# Konwerter_USB_RS232_4porty.net
KiCad netlist of a schematic drawn in Altium Designer
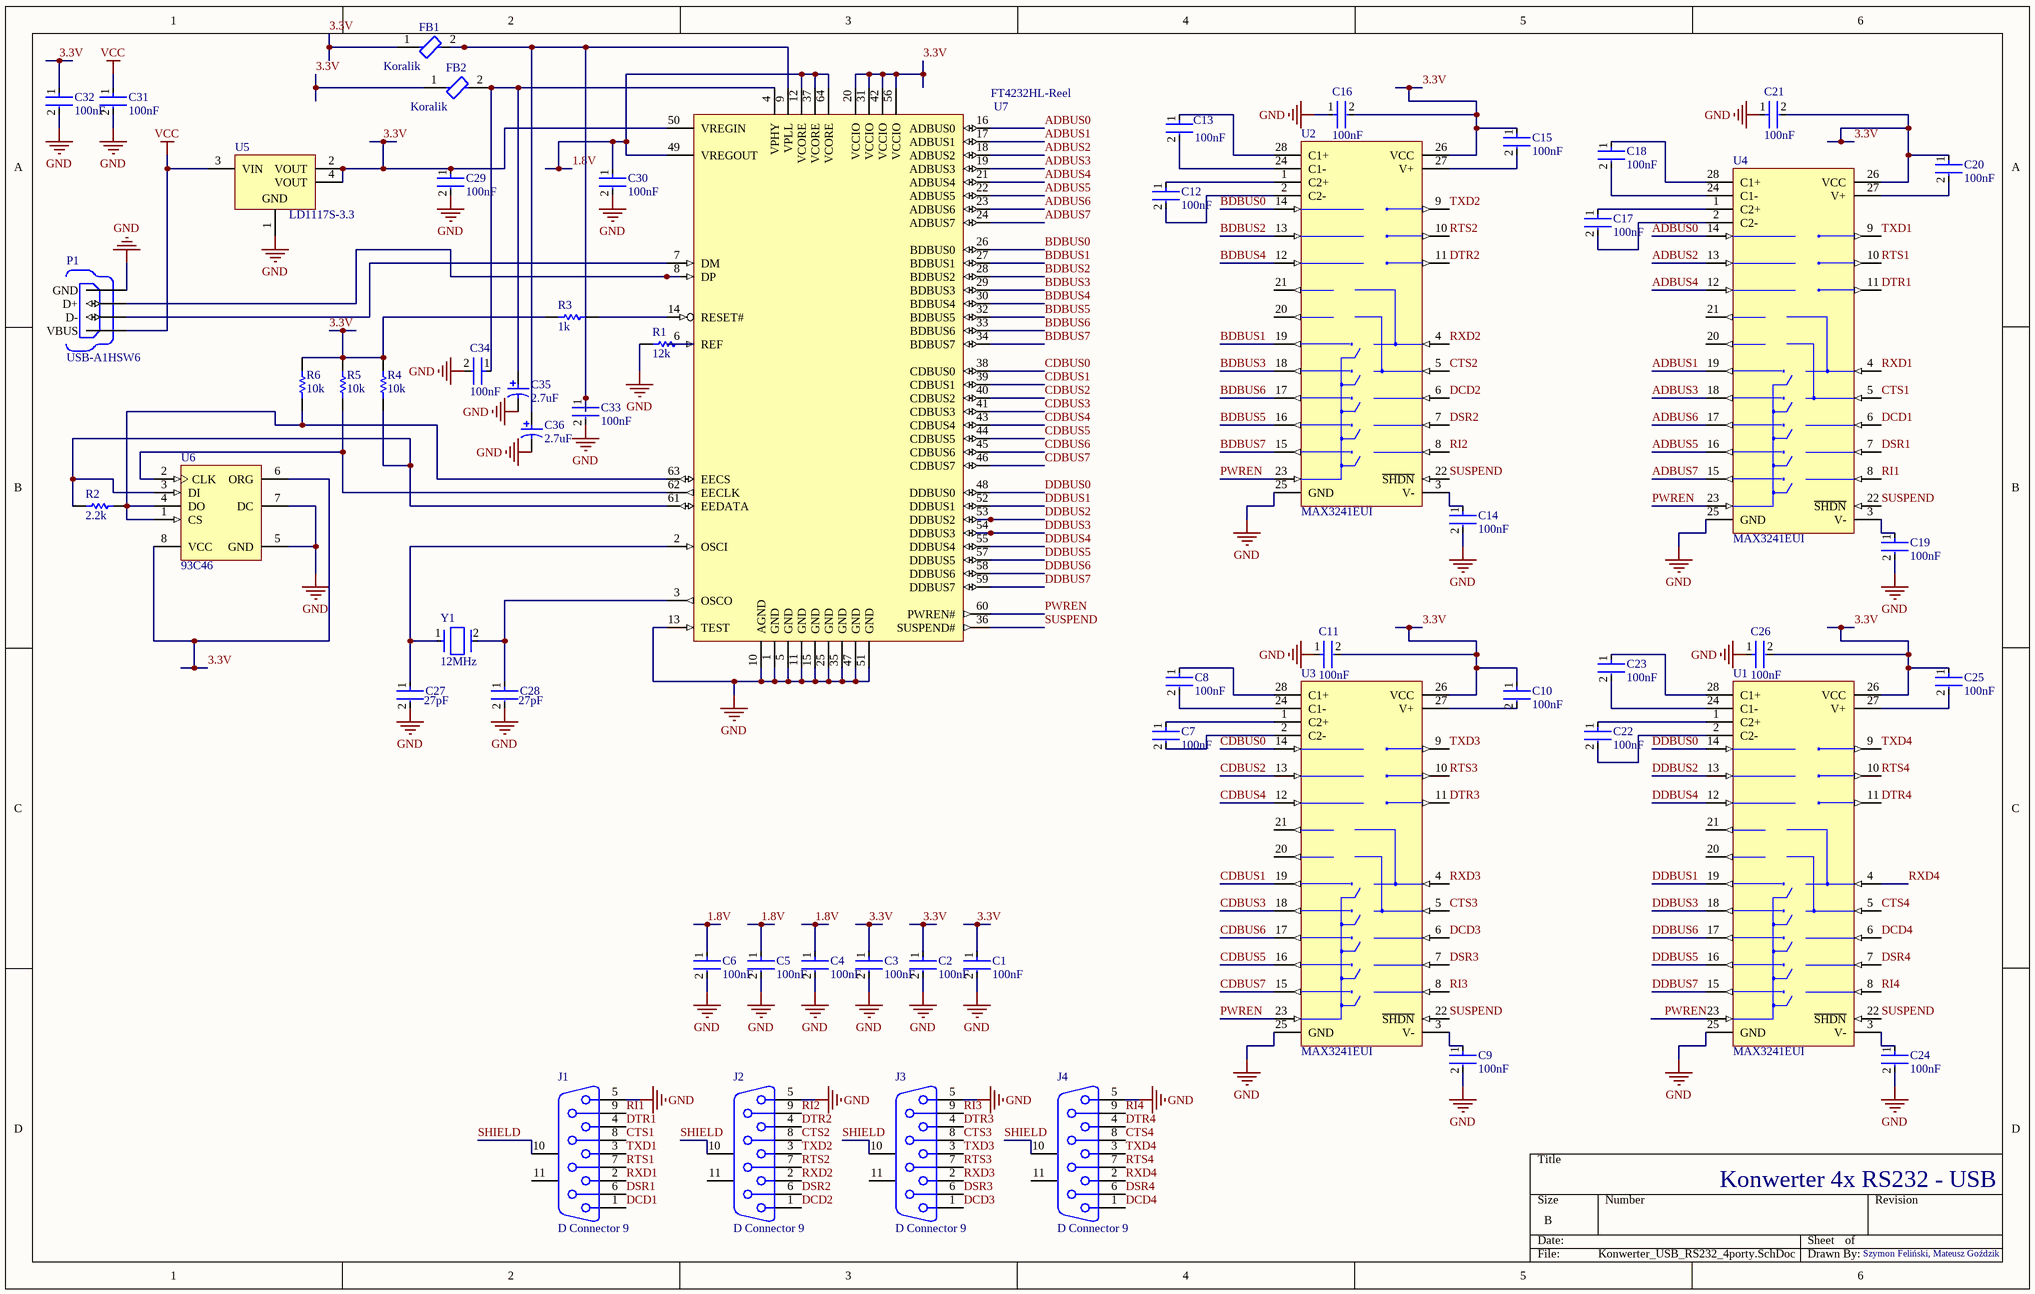
[diagram p0: Konwerter_USB_RS232_4porty.SchDoc]

(export (version "E")
  (design (tool "Eeschema 10.0.6"))
  (components
    (comp (ref "C1")
      (value "100nF")
      (footprint "FP-C0603C-CF-MFG")
      (description "CAP CER 0.1UF 50V X7R 0603")
      (fields (field (name "TOLERANCE") "0.1") (field (name "MANUFACTURER") "KEMET"))
      (libsource (lib "Altium Content Vault") (part "b4654b650e69147ec39a6b967a45e02"))
    )
    (comp (ref "C2")
      (value "100nF")
      (footprint "FP-C0603C-CF-MFG")
      (description "CAP CER 0.1UF 50V X7R 0603")
      (fields (field (name "TOLERANCE") "0.1") (field (name "MANUFACTURER") "KEMET"))
      (libsource (lib "Altium Content Vault") (part "b4654b650e69147ec39a6b967a45e02"))
    )
    (comp (ref "C3")
      (value "100nF")
      (footprint "FP-C0603C-CF-MFG")
      (description "CAP CER 0.1UF 50V X7R 0603")
      (fields (field (name "TOLERANCE") "0.1") (field (name "MANUFACTURER") "KEMET"))
      (libsource (lib "Altium Content Vault") (part "b4654b650e69147ec39a6b967a45e02"))
    )
    (comp (ref "C4")
      (value "100nF")
      (footprint "FP-C0603C-CF-MFG")
      (description "CAP CER 0.1UF 50V X7R 0603")
      (fields (field (name "TOLERANCE") "0.1") (field (name "MANUFACTURER") "KEMET"))
      (libsource (lib "Altium Content Vault") (part "b4654b650e69147ec39a6b967a45e02"))
    )
    (comp (ref "C5")
      (value "100nF")
      (footprint "FP-C0603C-CF-MFG")
      (description "CAP CER 0.1UF 50V X7R 0603")
      (fields (field (name "TOLERANCE") "0.1") (field (name "MANUFACTURER") "KEMET"))
      (libsource (lib "Altium Content Vault") (part "b4654b650e69147ec39a6b967a45e02"))
    )
    (comp (ref "C6")
      (value "100nF")
      (footprint "FP-C0603C-CF-MFG")
      (description "CAP CER 0.1UF 50V X7R 0603")
      (fields (field (name "TOLERANCE") "0.1") (field (name "MANUFACTURER") "KEMET"))
      (libsource (lib "Altium Content Vault") (part "b4654b650e69147ec39a6b967a45e02"))
    )
    (comp (ref "C7")
      (value "100nF")
      (footprint "FP-C0603C-CF-MFG")
      (description "CAP CER 0.1UF 50V X7R 0603")
      (fields (field (name "TOLERANCE") "0.1") (field (name "MANUFACTURER") "KEMET"))
      (libsource (lib "Altium Content Vault") (part "b4654b650e69147ec39a6b967a45e02"))
    )
    (comp (ref "C8")
      (value "100nF")
      (footprint "FP-C0603C-CF-MFG")
      (description "CAP CER 0.1UF 50V X7R 0603")
      (fields (field (name "TOLERANCE") "0.1") (field (name "MANUFACTURER") "KEMET"))
      (libsource (lib "Altium Content Vault") (part "b4654b650e69147ec39a6b967a45e02"))
    )
    (comp (ref "C9")
      (value "100nF")
      (footprint "FP-C0603C-CF-MFG")
      (description "CAP CER 0.1UF 50V X7R 0603")
      (fields (field (name "TOLERANCE") "0.1") (field (name "MANUFACTURER") "KEMET"))
      (libsource (lib "Altium Content Vault") (part "b4654b650e69147ec39a6b967a45e02"))
    )
    (comp (ref "C10")
      (value "100nF")
      (footprint "FP-C0603C-CF-MFG")
      (description "CAP CER 0.1UF 50V X7R 0603")
      (fields (field (name "TOLERANCE") "0.1") (field (name "MANUFACTURER") "KEMET"))
      (libsource (lib "Altium Content Vault") (part "b4654b650e69147ec39a6b967a45e02"))
    )
    (comp (ref "C11")
      (value "100nF")
      (footprint "FP-C0603C-CF-MFG")
      (description "CAP CER 0.1UF 50V X7R 0603")
      (fields (field (name "TOLERANCE") "0.1") (field (name "MANUFACTURER") "KEMET"))
      (libsource (lib "Altium Content Vault") (part "CMP-2006-03061-2"))
    )
    (comp (ref "C12")
      (value "100nF")
      (footprint "FP-C0603C-CF-MFG")
      (description "CAP CER 0.1UF 50V X7R 0603")
      (fields (field (name "TOLERANCE") "0.1") (field (name "MANUFACTURER") "KEMET"))
      (libsource (lib "Altium Content Vault") (part "b4654b650e69147ec39a6b967a45e02"))
    )
    (comp (ref "C13")
      (value "100nF")
      (footprint "FP-C0603C-CF-MFG")
      (description "CAP CER 0.1UF 50V X7R 0603")
      (fields (field (name "TOLERANCE") "0.1") (field (name "MANUFACTURER") "KEMET"))
      (libsource (lib "Altium Content Vault") (part "b4654b650e69147ec39a6b967a45e02"))
    )
    (comp (ref "C14")
      (value "100nF")
      (footprint "FP-C0603C-CF-MFG")
      (description "CAP CER 0.1UF 50V X7R 0603")
      (fields (field (name "TOLERANCE") "0.1") (field (name "MANUFACTURER") "KEMET"))
      (libsource (lib "Altium Content Vault") (part "CMP-2006-03061-2"))
    )
    (comp (ref "C15")
      (value "100nF")
      (footprint "FP-C0603C-CF-MFG")
      (description "CAP CER 0.1UF 50V X7R 0603")
      (fields (field (name "TOLERANCE") "0.1") (field (name "MANUFACTURER") "KEMET"))
      (libsource (lib "Altium Content Vault") (part "b4654b650e69147ec39a6b967a45e02"))
    )
    (comp (ref "C16")
      (value "100nF")
      (footprint "FP-C0603C-CF-MFG")
      (description "CAP CER 0.1UF 50V X7R 0603")
      (fields (field (name "TOLERANCE") "0.1") (field (name "MANUFACTURER") "KEMET"))
      (libsource (lib "Altium Content Vault") (part "b4654b650e69147ec39a6b967a45e02"))
    )
    (comp (ref "C17")
      (value "100nF")
      (footprint "FP-C0603C-CF-MFG")
      (description "CAP CER 0.1UF 50V X7R 0603")
      (fields (field (name "TOLERANCE") "0.1") (field (name "MANUFACTURER") "KEMET"))
      (libsource (lib "Altium Content Vault") (part "b4654b650e69147ec39a6b967a45e02"))
    )
    (comp (ref "C18")
      (value "100nF")
      (footprint "FP-C0603C-CF-MFG")
      (description "CAP CER 0.1UF 50V X7R 0603")
      (fields (field (name "TOLERANCE") "0.1") (field (name "MANUFACTURER") "KEMET"))
      (libsource (lib "Altium Content Vault") (part "b4654b650e69147ec39a6b967a45e02"))
    )
    (comp (ref "C19")
      (value "100nF")
      (footprint "FP-C0603C-CF-MFG")
      (description "CAP CER 0.1UF 50V X7R 0603")
      (fields (field (name "TOLERANCE") "0.1") (field (name "MANUFACTURER") "KEMET"))
      (libsource (lib "Altium Content Vault") (part "b4654b650e69147ec39a6b967a45e02"))
    )
    (comp (ref "C20")
      (value "100nF")
      (footprint "FP-C0603C-CF-MFG")
      (description "CAP CER 0.1UF 50V X7R 0603")
      (fields (field (name "TOLERANCE") "0.1") (field (name "MANUFACTURER") "KEMET"))
      (libsource (lib "Altium Content Vault") (part "b4654b650e69147ec39a6b967a45e02"))
    )
    (comp (ref "C21")
      (value "100nF")
      (footprint "FP-C0603C-CF-MFG")
      (description "CAP CER 0.1UF 50V X7R 0603")
      (fields (field (name "TOLERANCE") "0.1") (field (name "MANUFACTURER") "KEMET"))
      (libsource (lib "Altium Content Vault") (part "b4654b650e69147ec39a6b967a45e02"))
    )
    (comp (ref "C22")
      (value "100nF")
      (footprint "FP-C0603C-CF-MFG")
      (description "CAP CER 0.1UF 50V X7R 0603")
      (fields (field (name "TOLERANCE") "0.1") (field (name "MANUFACTURER") "KEMET"))
      (libsource (lib "Altium Content Vault") (part "b4654b650e69147ec39a6b967a45e02"))
    )
    (comp (ref "C23")
      (value "100nF")
      (footprint "FP-C0603C-CF-MFG")
      (description "CAP CER 0.1UF 50V X7R 0603")
      (fields (field (name "TOLERANCE") "0.1") (field (name "MANUFACTURER") "KEMET"))
      (libsource (lib "Altium Content Vault") (part "b4654b650e69147ec39a6b967a45e02"))
    )
    (comp (ref "C24")
      (value "100nF")
      (footprint "FP-C0603C-CF-MFG")
      (description "CAP CER 0.1UF 50V X7R 0603")
      (fields (field (name "TOLERANCE") "0.1") (field (name "MANUFACTURER") "KEMET"))
      (libsource (lib "Altium Content Vault") (part "b4654b650e69147ec39a6b967a45e02"))
    )
    (comp (ref "C25")
      (value "100nF")
      (footprint "FP-C0603C-CF-MFG")
      (description "CAP CER 0.1UF 50V X7R 0603")
      (fields (field (name "TOLERANCE") "0.1") (field (name "MANUFACTURER") "KEMET"))
      (libsource (lib "Altium Content Vault") (part "b4654b650e69147ec39a6b967a45e02"))
    )
    (comp (ref "C26")
      (value "100nF")
      (footprint "FP-C0603C-CF-MFG")
      (description "CAP CER 0.1UF 50V X7R 0603")
      (fields (field (name "TOLERANCE") "0.1") (field (name "MANUFACTURER") "KEMET"))
      (libsource (lib "Altium Content Vault") (part "CMP-2006-03061-2"))
    )
    (comp (ref "C27")
      (value "27pF")
      (footprint "FP-C0603C-CF-MFG")
      (description "CAP CER 0.1UF 50V X7R 0603")
      (fields (field (name "TOLERANCE") "0.1") (field (name "MANUFACTURER") "KEMET"))
      (libsource (lib "Altium Content Vault") (part "b4654b650e69147ec39a6b967a45e02"))
    )
    (comp (ref "C28")
      (value "27pF")
      (footprint "FP-C0603C-CF-MFG")
      (description "CAP CER 0.1UF 50V X7R 0603")
      (fields (field (name "TOLERANCE") "0.1") (field (name "MANUFACTURER") "KEMET"))
      (libsource (lib "Altium Content Vault") (part "b4654b650e69147ec39a6b967a45e02"))
    )
    (comp (ref "C29")
      (value "100nF")
      (footprint "FP-C0603C-CF-MFG")
      (description "CAP CER 0.1UF 50V X7R 0603")
      (fields (field (name "TOLERANCE") "0.1") (field (name "MANUFACTURER") "KEMET"))
      (libsource (lib "Altium Content Vault") (part "b4654b650e69147ec39a6b967a45e02"))
    )
    (comp (ref "C30")
      (value "100nF")
      (footprint "FP-C0603C-CF-MFG")
      (description "CAP CER 0.1UF 50V X7R 0603")
      (fields (field (name "TOLERANCE") "0.1") (field (name "MANUFACTURER") "KEMET"))
      (libsource (lib "Altium Content Vault") (part "b4654b650e69147ec39a6b967a45e02"))
    )
    (comp (ref "C31")
      (value "100nF")
      (footprint "FP-C0603C-CF-MFG")
      (description "CAP CER 0.1UF 50V X7R 0603")
      (fields (field (name "TOLERANCE") "0.1") (field (name "MANUFACTURER") "KEMET"))
      (libsource (lib "Altium Content Vault") (part "b4654b650e69147ec39a6b967a45e02"))
    )
    (comp (ref "C32")
      (value "100nF")
      (footprint "FP-C0603C-CF-MFG")
      (description "CAP CER 0.1UF 50V X7R 0603")
      (fields (field (name "TOLERANCE") "0.1") (field (name "MANUFACTURER") "KEMET"))
      (libsource (lib "Altium Content Vault") (part "b4654b650e69147ec39a6b967a45e02"))
    )
    (comp (ref "C33")
      (value "100nF")
      (footprint "FP-C0603C-CF-MFG")
      (description "CAP CER 0.1UF 50V X7R 0603")
      (fields (field (name "TOLERANCE") "0.1") (field (name "MANUFACTURER") "KEMET"))
      (libsource (lib "Altium Content Vault") (part "b4654b650e69147ec39a6b967a45e02"))
    )
    (comp (ref "C34")
      (value "100nF")
      (footprint "FP-C0603C-CF-MFG")
      (description "CAP CER 0.1UF 50V X7R 0603")
      (fields (field (name "TOLERANCE") "0.1") (field (name "MANUFACTURER") "KEMET"))
      (libsource (lib "Altium Content Vault") (part "b4654b650e69147ec39a6b967a45e02"))
    )
    (comp (ref "C35")
      (value "2.7uF")
      (footprint "NIC-UCL1V101MNL1GS_L")
      (fields (field (name "MANUFACTURER") "Nichicon") (field (name "TOLERANCE") "20%"))
      (libsource (lib "Altium Content Vault") (part "CAP-P-2"))
    )
    (comp (ref "C36")
      (value "2.7uF")
      (footprint "NIC-UCL1V101MNL1GS_L")
      (fields (field (name "MANUFACTURER") "Nichicon") (field (name "TOLERANCE") "20%"))
      (libsource (lib "Altium Content Vault") (part "CAP-P-2"))
    )
    (comp (ref "FB1")
      (value "Koralik")
      (footprint "FP-BLM15-0_05-IPC_A")
      (description "Chip Ferrite Bead, 0402, 220Ω @ 100MHz, 0.18Ω, 25%, 600mA")
      (fields (field (name "TOLERANCE") "25%"))
      (libsource (lib "Altium Content Vault") (part "CMP-0686-00232-4"))
    )
    (comp (ref "FB2")
      (value "Koralik")
      (footprint "FP-BLM15-0_05-IPC_A")
      (description "Chip Ferrite Bead, 0402, 220Ω @ 100MHz, 0.18Ω, 25%, 600mA")
      (fields (field (name "TOLERANCE") "25%"))
      (libsource (lib "Altium Content Vault") (part "5f30dd21d616792df468990f7003faa"))
    )
    (comp (ref "J1")
      (value "D Connector 9")
      (footprint "DSUB1.385-2H9")
      (description "Receptacle Assembly, 9 Position, Right Angle")
      (fields (field (name "PUBLISHER") "Altium Limited"))
      (libsource (lib "Miscellaneous Connectors") (part "D Connector 9"))
    )
    (comp (ref "J2")
      (value "D Connector 9")
      (footprint "DSUB1.385-2H9")
      (description "Receptacle Assembly, 9 Position, Right Angle")
      (fields (field (name "PUBLISHER") "Altium Limited"))
      (libsource (lib "Miscellaneous Connectors") (part "D Connector 9"))
    )
    (comp (ref "J3")
      (value "D Connector 9")
      (footprint "DSUB1.385-2H9")
      (description "Receptacle Assembly, 9 Position, Right Angle")
      (fields (field (name "PUBLISHER") "Altium Limited"))
      (libsource (lib "Miscellaneous Connectors") (part "D Connector 9"))
    )
    (comp (ref "J4")
      (value "D Connector 9")
      (footprint "DSUB1.385-2H9")
      (description "Receptacle Assembly, 9 Position, Right Angle")
      (fields (field (name "PUBLISHER") "Altium Limited"))
      (libsource (lib "Miscellaneous Connectors") (part "D Connector 9"))
    )
    (comp (ref "P1")
      (value "USB-A1HSW6")
      (footprint "OST_USB-A1HSW6")
      (description "USB-A _USB TYPE-A_  Receptacle Connector 4 Position Through Hole, Right Angle")
      (fields (field (name "MF") "On Shore"))
      (libsource (lib "USB-A1HSW6") (part "USB-A1HSW6"))
    )
    (comp (ref "R1")
      (value "12k")
      (footprint "RESC2013X50X30LL20T20")
      (fields (field (name "MANUFACTURER") "Vishay Dale") (field (name "PART NUMBER") "CRCW08050000Z0EA"))
      (libsource (lib "Altium Content Vault") (part "RES"))
    )
    (comp (ref "R2")
      (value "2.2k")
      (footprint "RESC2013X50X30LL20T20")
      (fields (field (name "MANUFACTURER") "Vishay Dale") (field (name "PART NUMBER") "CRCW08050000Z0EA"))
      (libsource (lib "Altium Content Vault") (part "RES"))
    )
    (comp (ref "R3")
      (value "1k")
      (footprint "RESC2013X50X30LL20T20")
      (fields (field (name "MANUFACTURER") "Vishay Dale") (field (name "PART NUMBER") "CRCW08050000Z0EA"))
      (libsource (lib "Altium Content Vault") (part "RES"))
    )
    (comp (ref "R4")
      (value "10k")
      (footprint "RESC2013X50X30LL20T20")
      (fields (field (name "MANUFACTURER") "Vishay Dale") (field (name "PART NUMBER") "CRCW08050000Z0EA"))
      (libsource (lib "Altium Content Vault") (part "RES"))
    )
    (comp (ref "R5")
      (value "10k")
      (footprint "RESC2013X50X30LL20T20")
      (fields (field (name "MANUFACTURER") "Vishay Dale") (field (name "PART NUMBER") "CRCW08050000Z0EA"))
      (libsource (lib "Altium Content Vault") (part "RES"))
    )
    (comp (ref "R6")
      (value "10k")
      (footprint "RESC2013X50X30LL20T20")
      (fields (field (name "MANUFACTURER") "Vishay Dale") (field (name "PART NUMBER") "CRCW08050000Z0EA"))
      (libsource (lib "Altium Content Vault") (part "RES"))
    )
    (comp (ref "U1")
      (value "MAX3241EUI")
      (footprint "TSSOP28_N")
      (description "3.0V TO 5.5V, Low-Power, up to 1Mbps, True RS-232 Transceiver Using Four 0.1µF External Capacitor")
      (fields (field (name "PUBLISHER") "Altium Limited"))
      (libsource (lib "Maxim Communication Transceiver") (part "MAX3241EUI"))
    )
    (comp (ref "U2")
      (value "MAX3241EUI")
      (footprint "TSSOP28_N")
      (description "3.0V TO 5.5V, Low-Power, up to 1Mbps, True RS-232 Transceiver Using Four 0.1µF External Capacitor")
      (fields (field (name "PUBLISHER") "Altium Limited"))
      (libsource (lib "Maxim Communication Transceiver") (part "MAX3241EUI"))
    )
    (comp (ref "U3")
      (value "MAX3241EUI")
      (footprint "TSSOP28_N")
      (description "3.0V TO 5.5V, Low-Power, up to 1Mbps, True RS-232 Transceiver Using Four 0.1µF External Capacitor")
      (fields (field (name "PUBLISHER") "Altium Limited"))
      (libsource (lib "Maxim Communication Transceiver") (part "MAX3241EUI"))
    )
    (comp (ref "U4")
      (value "MAX3241EUI")
      (footprint "TSSOP28_N")
      (description "3.0V TO 5.5V, Low-Power, up to 1Mbps, True RS-232 Transceiver Using Four 0.1µF External Capacitor")
      (fields (field (name "PUBLISHER") "Altium Limited"))
      (libsource (lib "Maxim Communication Transceiver") (part "MAX3241EUI"))
    )
    (comp (ref "U5")
      (value "LD1117S-3.3")
      (footprint "SOT-223_L")
      (description "Fixed Low Drop Positive Voltage Regulator, 3.3V, 4-Pin SOT-223, Tape and Reel")
      (libsource (lib "Altium Content Vault") (part "PM-REG-LD1117-SOT4"))
    )
    (comp (ref "U6")
      (value "93C46")
      (footprint "ATML-8S1_B_L")
      (description "Three-Wire Serial EEPROM, 2.7 to 5.5 V, -40 to 85 degC, 8-Pin SOIC, RoHS, Tube")
      (fields (field (name "MANUFACTURER") "Atmel"))
      (libsource (lib "Altium Content Vault") (part "ATML-AT93C46-SOIC-8"))
    )
    (comp (ref "U7")
      (value "FT4232HL-Reel")
      (footprint "LQFP-64_N")
      (description "Quad High Speed USB To Multipurpose UART/MPSSE IC, LQFP-64, Tape and Reel")
      (fields (field (name "PUBLISHER") "Altium Limited"))
      (libsource (lib "FTDI Communication UART") (part "FT4232HL-Reel"))
    )
    (comp (ref "Y1")
      (value "12MHz")
      (footprint "FP-7A-MFG")
      (description "Quartz Crystal 48MHz, 30ppm, 12pF, 50Ω")
      (fields (field (name "TOLERANCE") "30ppm"))
      (libsource (lib "Altium Content Vault") (part "c23a69dc6c9e2f18f2079038eb95dd1"))
    )
  )
  (nets
    (net (code "1") (name "/1.8V") (class "Default")
      (node (ref "C30") (pin "1") (pinfunction "1_1") (pintype "passive"))
      (node (ref "C4") (pin "1") (pinfunction "1_1") (pintype "passive"))
      (node (ref "C5") (pin "1") (pinfunction "1_1") (pintype "passive"))
      (node (ref "C6") (pin "1") (pinfunction "1_1") (pintype "passive"))
      (node (ref "U7") (pin "12") (pinfunction "VCORE_12") (pintype "power_in"))
      (node (ref "U7") (pin "37") (pinfunction "VCORE_37") (pintype "power_in"))
      (node (ref "U7") (pin "49") (pinfunction "VREGOUT_49") (pintype "power_in"))
      (node (ref "U7") (pin "64") (pinfunction "VCORE_64") (pintype "power_in"))
    )
    (net (code "2") (name "/3.3V") (class "Default")
      (node (ref "C1") (pin "1") (pinfunction "1_1") (pintype "passive"))
      (node (ref "C10") (pin "1") (pinfunction "1_1") (pintype "passive"))
      (node (ref "C11") (pin "2") (pinfunction "2_2") (pintype "passive"))
      (node (ref "C15") (pin "1") (pinfunction "1_1") (pintype "passive"))
      (node (ref "C16") (pin "2") (pinfunction "2_2") (pintype "passive"))
      (node (ref "C2") (pin "1") (pinfunction "1_1") (pintype "passive"))
      (node (ref "C20") (pin "1") (pinfunction "1_1") (pintype "passive"))
      (node (ref "C21") (pin "2") (pinfunction "2_2") (pintype "passive"))
      (node (ref "C25") (pin "1") (pinfunction "1_1") (pintype "passive"))
      (node (ref "C26") (pin "2") (pinfunction "2_2") (pintype "passive"))
      (node (ref "C29") (pin "1") (pinfunction "1_1") (pintype "passive"))
      (node (ref "C3") (pin "1") (pinfunction "1_1") (pintype "passive"))
      (node (ref "C32") (pin "1") (pinfunction "1_1") (pintype "passive"))
      (node (ref "FB1") (pin "1") (pinfunction "1_1") (pintype "passive"))
      (node (ref "FB2") (pin "1") (pinfunction "1_1") (pintype "passive"))
      (node (ref "R3") (pin "1") (pinfunction "1_1") (pintype "passive"))
      (node (ref "R4") (pin "2") (pinfunction "2_2") (pintype "passive"))
      (node (ref "R5") (pin "2") (pinfunction "2_2") (pintype "passive"))
      (node (ref "R6") (pin "2") (pinfunction "2_2") (pintype "passive"))
      (node (ref "U1") (pin "26") (pinfunction "VCC_26") (pintype "power_in"))
      (node (ref "U2") (pin "26") (pinfunction "VCC_26") (pintype "power_in"))
      (node (ref "U3") (pin "26") (pinfunction "VCC_26") (pintype "power_in"))
      (node (ref "U4") (pin "26") (pinfunction "VCC_26") (pintype "power_in"))
      (node (ref "U5") (pin "2") (pinfunction "VOUT_2") (pintype "power_in"))
      (node (ref "U5") (pin "4") (pinfunction "VOUT_4") (pintype "power_in"))
      (node (ref "U6") (pin "6") (pinfunction "ORG_6") (pintype "passive"))
      (node (ref "U6") (pin "8") (pinfunction "VCC_8") (pintype "power_in"))
      (node (ref "U7") (pin "20") (pinfunction "VCCIO_20") (pintype "power_in"))
      (node (ref "U7") (pin "31") (pinfunction "VCCIO_31") (pintype "power_in"))
      (node (ref "U7") (pin "42") (pinfunction "VCCIO_42") (pintype "power_in"))
      (node (ref "U7") (pin "50") (pinfunction "VREGIN_50") (pintype "power_in"))
      (node (ref "U7") (pin "56") (pinfunction "VCCIO_56") (pintype "power_in"))
    )
    (net (code "3") (name "/ADBUS0") (class "Default")
      (node (ref "U4") (pin "14") (pinfunction "T1IN_14") (pintype "input"))
      (node (ref "U7") (pin "16") (pinfunction "ADBUS0_16") (pintype "bidirectional"))
    )
    (net (code "4") (name "/ADBUS1") (class "Default")
      (node (ref "U4") (pin "19") (pinfunction "R1OUT_19") (pintype "output"))
      (node (ref "U7") (pin "17") (pinfunction "ADBUS1_17") (pintype "bidirectional"))
    )
    (net (code "5") (name "/ADBUS2") (class "Default")
      (node (ref "U4") (pin "13") (pinfunction "T2IN_13") (pintype "input"))
      (node (ref "U7") (pin "18") (pinfunction "ADBUS2_18") (pintype "bidirectional"))
    )
    (net (code "6") (name "/ADBUS3") (class "Default")
      (node (ref "U4") (pin "18") (pinfunction "R2OUT_18") (pintype "output"))
      (node (ref "U7") (pin "19") (pinfunction "ADBUS3_19") (pintype "bidirectional"))
    )
    (net (code "7") (name "/ADBUS4") (class "Default")
      (node (ref "U4") (pin "12") (pinfunction "T3IN_12") (pintype "input"))
      (node (ref "U7") (pin "21") (pinfunction "ADBUS4_21") (pintype "bidirectional"))
    )
    (net (code "8") (name "/ADBUS5") (class "Default")
      (node (ref "U4") (pin "16") (pinfunction "R4OUT_16") (pintype "output"))
      (node (ref "U7") (pin "22") (pinfunction "ADBUS5_22") (pintype "bidirectional"))
    )
    (net (code "9") (name "/ADBUS6") (class "Default")
      (node (ref "U4") (pin "17") (pinfunction "R3OUT_17") (pintype "output"))
      (node (ref "U7") (pin "23") (pinfunction "ADBUS6_23") (pintype "bidirectional"))
    )
    (net (code "10") (name "/ADBUS7") (class "Default")
      (node (ref "U4") (pin "15") (pinfunction "R5OUT_15") (pintype "output"))
      (node (ref "U7") (pin "24") (pinfunction "ADBUS7_24") (pintype "bidirectional"))
    )
    (net (code "11") (name "/BDBUS0") (class "Default")
      (node (ref "U2") (pin "14") (pinfunction "T1IN_14") (pintype "input"))
      (node (ref "U7") (pin "26") (pinfunction "BDBUS0_26") (pintype "bidirectional"))
    )
    (net (code "12") (name "/BDBUS1") (class "Default")
      (node (ref "U2") (pin "19") (pinfunction "R1OUT_19") (pintype "output"))
      (node (ref "U7") (pin "27") (pinfunction "BDBUS1_27") (pintype "bidirectional"))
    )
    (net (code "13") (name "/BDBUS2") (class "Default")
      (node (ref "U2") (pin "13") (pinfunction "T2IN_13") (pintype "input"))
      (node (ref "U7") (pin "28") (pinfunction "BDBUS2_28") (pintype "bidirectional"))
    )
    (net (code "14") (name "/BDBUS3") (class "Default")
      (node (ref "U2") (pin "18") (pinfunction "R2OUT_18") (pintype "output"))
      (node (ref "U7") (pin "29") (pinfunction "BDBUS3_29") (pintype "bidirectional"))
    )
    (net (code "15") (name "/BDBUS4") (class "Default")
      (node (ref "U2") (pin "12") (pinfunction "T3IN_12") (pintype "input"))
      (node (ref "U7") (pin "30") (pinfunction "BDBUS4_30") (pintype "bidirectional"))
    )
    (net (code "16") (name "/BDBUS5") (class "Default")
      (node (ref "U2") (pin "16") (pinfunction "R4OUT_16") (pintype "output"))
      (node (ref "U7") (pin "32") (pinfunction "BDBUS5_32") (pintype "bidirectional"))
    )
    (net (code "17") (name "/BDBUS6") (class "Default")
      (node (ref "U2") (pin "17") (pinfunction "R3OUT_17") (pintype "output"))
      (node (ref "U7") (pin "33") (pinfunction "BDBUS6_33") (pintype "bidirectional"))
    )
    (net (code "18") (name "/BDBUS7") (class "Default")
      (node (ref "U2") (pin "15") (pinfunction "R5OUT_15") (pintype "output"))
      (node (ref "U7") (pin "34") (pinfunction "BDBUS7_34") (pintype "bidirectional"))
    )
    (net (code "19") (name "/CDBUS0") (class "Default")
      (node (ref "U3") (pin "14") (pinfunction "T1IN_14") (pintype "input"))
      (node (ref "U7") (pin "38") (pinfunction "CDBUS0_38") (pintype "bidirectional"))
    )
    (net (code "20") (name "/CDBUS1") (class "Default")
      (node (ref "U3") (pin "19") (pinfunction "R1OUT_19") (pintype "output"))
      (node (ref "U7") (pin "39") (pinfunction "CDBUS1_39") (pintype "bidirectional"))
    )
    (net (code "21") (name "/CDBUS2") (class "Default")
      (node (ref "U3") (pin "13") (pinfunction "T2IN_13") (pintype "input"))
      (node (ref "U7") (pin "40") (pinfunction "CDBUS2_40") (pintype "bidirectional"))
    )
    (net (code "22") (name "/CDBUS3") (class "Default")
      (node (ref "U3") (pin "18") (pinfunction "R2OUT_18") (pintype "output"))
      (node (ref "U7") (pin "41") (pinfunction "CDBUS3_41") (pintype "bidirectional"))
    )
    (net (code "23") (name "/CDBUS4") (class "Default")
      (node (ref "U3") (pin "12") (pinfunction "T3IN_12") (pintype "input"))
      (node (ref "U7") (pin "43") (pinfunction "CDBUS4_43") (pintype "bidirectional"))
    )
    (net (code "24") (name "/CDBUS5") (class "Default")
      (node (ref "U3") (pin "16") (pinfunction "R4OUT_16") (pintype "output"))
      (node (ref "U7") (pin "44") (pinfunction "CDBUS5_44") (pintype "bidirectional"))
    )
    (net (code "25") (name "/CDBUS6") (class "Default")
      (node (ref "U3") (pin "17") (pinfunction "R3OUT_17") (pintype "output"))
      (node (ref "U7") (pin "45") (pinfunction "CDBUS6_45") (pintype "bidirectional"))
    )
    (net (code "26") (name "/CDBUS7") (class "Default")
      (node (ref "U3") (pin "15") (pinfunction "R5OUT_15") (pintype "output"))
      (node (ref "U7") (pin "46") (pinfunction "CDBUS7_46") (pintype "bidirectional"))
    )
    (net (code "27") (name "/CTS1") (class "Default")
      (node (ref "J1") (pin "8") (pinfunction "8_8") (pintype "passive"))
      (node (ref "U4") (pin "5") (pinfunction "R2IN_5") (pintype "input"))
    )
    (net (code "28") (name "/CTS2") (class "Default")
      (node (ref "J2") (pin "8") (pinfunction "8_8") (pintype "passive"))
      (node (ref "U2") (pin "5") (pinfunction "R2IN_5") (pintype "input"))
    )
    (net (code "29") (name "/CTS3") (class "Default")
      (node (ref "J3") (pin "8") (pinfunction "8_8") (pintype "passive"))
      (node (ref "U3") (pin "5") (pinfunction "R2IN_5") (pintype "input"))
    )
    (net (code "30") (name "/CTS4") (class "Default")
      (node (ref "J4") (pin "8") (pinfunction "8_8") (pintype "passive"))
      (node (ref "U1") (pin "5") (pinfunction "R2IN_5") (pintype "input"))
    )
    (net (code "31") (name "/DCD1") (class "Default")
      (node (ref "J1") (pin "1") (pinfunction "1_1") (pintype "passive"))
      (node (ref "U4") (pin "6") (pinfunction "R3IN_6") (pintype "input"))
    )
    (net (code "32") (name "/DCD2") (class "Default")
      (node (ref "J2") (pin "1") (pinfunction "1_1") (pintype "passive"))
      (node (ref "U2") (pin "6") (pinfunction "R3IN_6") (pintype "input"))
    )
    (net (code "33") (name "/DCD3") (class "Default")
      (node (ref "J3") (pin "1") (pinfunction "1_1") (pintype "passive"))
      (node (ref "U3") (pin "6") (pinfunction "R3IN_6") (pintype "input"))
    )
    (net (code "34") (name "/DCD4") (class "Default")
      (node (ref "J4") (pin "1") (pinfunction "1_1") (pintype "passive"))
      (node (ref "U1") (pin "6") (pinfunction "R3IN_6") (pintype "input"))
    )
    (net (code "35") (name "/DDBUS0") (class "Default")
      (node (ref "U1") (pin "14") (pinfunction "T1IN_14") (pintype "input"))
      (node (ref "U7") (pin "48") (pinfunction "DDBUS0_48") (pintype "bidirectional"))
    )
    (net (code "36") (name "/DDBUS1") (class "Default")
      (node (ref "U1") (pin "19") (pinfunction "R1OUT_19") (pintype "output"))
      (node (ref "U7") (pin "52") (pinfunction "DDBUS1_52") (pintype "bidirectional"))
    )
    (net (code "37") (name "/DDBUS2") (class "Default")
      (node (ref "U1") (pin "13") (pinfunction "T2IN_13") (pintype "input"))
      (node (ref "U7") (pin "53") (pinfunction "DDBUS2_53") (pintype "bidirectional"))
    )
    (net (code "38") (name "/DDBUS3") (class "Default")
      (node (ref "U1") (pin "18") (pinfunction "R2OUT_18") (pintype "output"))
      (node (ref "U7") (pin "54") (pinfunction "DDBUS3_54") (pintype "bidirectional"))
    )
    (net (code "39") (name "/DDBUS4") (class "Default")
      (node (ref "U1") (pin "12") (pinfunction "T3IN_12") (pintype "input"))
      (node (ref "U7") (pin "55") (pinfunction "DDBUS4_55") (pintype "bidirectional"))
    )
    (net (code "40") (name "/DDBUS5") (class "Default")
      (node (ref "U1") (pin "16") (pinfunction "R4OUT_16") (pintype "output"))
      (node (ref "U7") (pin "57") (pinfunction "DDBUS5_57") (pintype "bidirectional"))
    )
    (net (code "41") (name "/DDBUS6") (class "Default")
      (node (ref "U1") (pin "17") (pinfunction "R3OUT_17") (pintype "output"))
      (node (ref "U7") (pin "58") (pinfunction "DDBUS6_58") (pintype "bidirectional"))
    )
    (net (code "42") (name "/DDBUS7") (class "Default")
      (node (ref "U1") (pin "15") (pinfunction "R5OUT_15") (pintype "output"))
      (node (ref "U7") (pin "59") (pinfunction "DDBUS7_59") (pintype "bidirectional"))
    )
    (net (code "43") (name "/DSR1") (class "Default")
      (node (ref "J1") (pin "6") (pinfunction "6_6") (pintype "passive"))
      (node (ref "U4") (pin "7") (pinfunction "R4IN_7") (pintype "input"))
    )
    (net (code "44") (name "/DSR2") (class "Default")
      (node (ref "J2") (pin "6") (pinfunction "6_6") (pintype "passive"))
      (node (ref "U2") (pin "7") (pinfunction "R4IN_7") (pintype "input"))
    )
    (net (code "45") (name "/DSR3") (class "Default")
      (node (ref "J3") (pin "6") (pinfunction "6_6") (pintype "passive"))
      (node (ref "U3") (pin "7") (pinfunction "R4IN_7") (pintype "input"))
    )
    (net (code "46") (name "/DSR4") (class "Default")
      (node (ref "J4") (pin "6") (pinfunction "6_6") (pintype "passive"))
      (node (ref "U1") (pin "7") (pinfunction "R4IN_7") (pintype "input"))
    )
    (net (code "47") (name "/DTR1") (class "Default")
      (node (ref "J1") (pin "4") (pinfunction "4_4") (pintype "passive"))
      (node (ref "U4") (pin "11") (pinfunction "T3OUT_11") (pintype "output"))
    )
    (net (code "48") (name "/DTR2") (class "Default")
      (node (ref "J2") (pin "4") (pinfunction "4_4") (pintype "passive"))
      (node (ref "U2") (pin "11") (pinfunction "T3OUT_11") (pintype "output"))
    )
    (net (code "49") (name "/DTR3") (class "Default")
      (node (ref "J3") (pin "4") (pinfunction "4_4") (pintype "passive"))
      (node (ref "U3") (pin "11") (pinfunction "T3OUT_11") (pintype "output"))
    )
    (net (code "50") (name "/DTR4") (class "Default")
      (node (ref "J4") (pin "4") (pinfunction "4_4") (pintype "passive"))
      (node (ref "U1") (pin "11") (pinfunction "T3OUT_11") (pintype "output"))
    )
    (net (code "51") (name "/PWREN") (class "Default")
      (node (ref "U1") (pin "23") (pinfunction "~{EN}_23") (pintype "input"))
      (node (ref "U2") (pin "23") (pinfunction "~{EN}_23") (pintype "input"))
      (node (ref "U3") (pin "23") (pinfunction "~{EN}_23") (pintype "input"))
      (node (ref "U4") (pin "23") (pinfunction "~{EN}_23") (pintype "input"))
      (node (ref "U7") (pin "60") (pinfunction "PWREN#_60") (pintype "output"))
    )
    (net (code "52") (name "/RI1") (class "Default")
      (node (ref "J1") (pin "9") (pinfunction "9_9") (pintype "passive"))
      (node (ref "U4") (pin "8") (pinfunction "R5IN_8") (pintype "input"))
    )
    (net (code "53") (name "/RI2") (class "Default")
      (node (ref "J2") (pin "9") (pinfunction "9_9") (pintype "passive"))
      (node (ref "U2") (pin "8") (pinfunction "R5IN_8") (pintype "input"))
    )
    (net (code "54") (name "/RI3") (class "Default")
      (node (ref "J3") (pin "9") (pinfunction "9_9") (pintype "passive"))
      (node (ref "U3") (pin "8") (pinfunction "R5IN_8") (pintype "input"))
    )
    (net (code "55") (name "/RI4") (class "Default")
      (node (ref "J4") (pin "9") (pinfunction "9_9") (pintype "passive"))
      (node (ref "U1") (pin "8") (pinfunction "R5IN_8") (pintype "input"))
    )
    (net (code "56") (name "/RTS1") (class "Default")
      (node (ref "J1") (pin "7") (pinfunction "7_7") (pintype "passive"))
      (node (ref "U4") (pin "10") (pinfunction "T2OUT_10") (pintype "output"))
    )
    (net (code "57") (name "/RTS2") (class "Default")
      (node (ref "J2") (pin "7") (pinfunction "7_7") (pintype "passive"))
      (node (ref "U2") (pin "10") (pinfunction "T2OUT_10") (pintype "output"))
    )
    (net (code "58") (name "/RTS3") (class "Default")
      (node (ref "J3") (pin "7") (pinfunction "7_7") (pintype "passive"))
      (node (ref "U3") (pin "10") (pinfunction "T2OUT_10") (pintype "output"))
    )
    (net (code "59") (name "/RTS4") (class "Default")
      (node (ref "J4") (pin "7") (pinfunction "7_7") (pintype "passive"))
      (node (ref "U1") (pin "10") (pinfunction "T2OUT_10") (pintype "output"))
    )
    (net (code "60") (name "/RXD1") (class "Default")
      (node (ref "J1") (pin "2") (pinfunction "2_2") (pintype "passive"))
      (node (ref "U4") (pin "4") (pinfunction "R1IN_4") (pintype "input"))
    )
    (net (code "61") (name "/RXD2") (class "Default")
      (node (ref "J2") (pin "2") (pinfunction "2_2") (pintype "passive"))
      (node (ref "U2") (pin "4") (pinfunction "R1IN_4") (pintype "input"))
    )
    (net (code "62") (name "/RXD3") (class "Default")
      (node (ref "J3") (pin "2") (pinfunction "2_2") (pintype "passive"))
      (node (ref "U3") (pin "4") (pinfunction "R1IN_4") (pintype "input"))
    )
    (net (code "63") (name "/RXD4") (class "Default")
      (node (ref "J4") (pin "2") (pinfunction "2_2") (pintype "passive"))
      (node (ref "U1") (pin "4") (pinfunction "R1IN_4") (pintype "input"))
    )
    (net (code "64") (name "/SHIELD") (class "Default")
      (node (ref "J1") (pin "10") (pinfunction "MH1_10") (pintype "passive"))
      (node (ref "J2") (pin "10") (pinfunction "MH1_10") (pintype "passive"))
      (node (ref "J3") (pin "10") (pinfunction "MH1_10") (pintype "passive"))
      (node (ref "J4") (pin "10") (pinfunction "MH1_10") (pintype "passive"))
    )
    (net (code "65") (name "/SUSPEND") (class "Default")
      (node (ref "U1") (pin "22") (pinfunction "~{SHDN}_22") (pintype "input"))
      (node (ref "U2") (pin "22") (pinfunction "~{SHDN}_22") (pintype "input"))
      (node (ref "U3") (pin "22") (pinfunction "~{SHDN}_22") (pintype "input"))
      (node (ref "U4") (pin "22") (pinfunction "~{SHDN}_22") (pintype "input"))
      (node (ref "U7") (pin "36") (pinfunction "SUSPEND#_36") (pintype "output"))
    )
    (net (code "66") (name "/TXD1") (class "Default")
      (node (ref "J1") (pin "3") (pinfunction "3_3") (pintype "passive"))
      (node (ref "U4") (pin "9") (pinfunction "T1OUT_9") (pintype "output"))
    )
    (net (code "67") (name "/TXD2") (class "Default")
      (node (ref "J2") (pin "3") (pinfunction "3_3") (pintype "passive"))
      (node (ref "U2") (pin "9") (pinfunction "T1OUT_9") (pintype "output"))
    )
    (net (code "68") (name "/TXD3") (class "Default")
      (node (ref "J3") (pin "3") (pinfunction "3_3") (pintype "passive"))
      (node (ref "U3") (pin "9") (pinfunction "T1OUT_9") (pintype "output"))
    )
    (net (code "69") (name "/TXD4") (class "Default")
      (node (ref "J4") (pin "3") (pinfunction "3_3") (pintype "passive"))
      (node (ref "U1") (pin "9") (pinfunction "T1OUT_9") (pintype "output"))
    )
    (net (code "70") (name "GND") (class "Default")
      (node (ref "C1") (pin "2") (pinfunction "2_2") (pintype "passive"))
      (node (ref "C11") (pin "1") (pinfunction "1_1") (pintype "passive"))
      (node (ref "C14") (pin "2") (pinfunction "2_2") (pintype "passive"))
      (node (ref "C16") (pin "1") (pinfunction "1_1") (pintype "passive"))
      (node (ref "C19") (pin "2") (pinfunction "2_2") (pintype "passive"))
      (node (ref "C2") (pin "2") (pinfunction "2_2") (pintype "passive"))
      (node (ref "C21") (pin "1") (pinfunction "1_1") (pintype "passive"))
      (node (ref "C24") (pin "2") (pinfunction "2_2") (pintype "passive"))
      (node (ref "C26") (pin "1") (pinfunction "1_1") (pintype "passive"))
      (node (ref "C27") (pin "2") (pinfunction "2_2") (pintype "passive"))
      (node (ref "C28") (pin "2") (pinfunction "2_2") (pintype "passive"))
      (node (ref "C29") (pin "2") (pinfunction "2_2") (pintype "passive"))
      (node (ref "C3") (pin "2") (pinfunction "2_2") (pintype "passive"))
      (node (ref "C30") (pin "2") (pinfunction "2_2") (pintype "passive"))
      (node (ref "C31") (pin "2") (pinfunction "2_2") (pintype "passive"))
      (node (ref "C32") (pin "2") (pinfunction "2_2") (pintype "passive"))
      (node (ref "C33") (pin "2") (pinfunction "2_2") (pintype "passive"))
      (node (ref "C34") (pin "2") (pinfunction "2_2") (pintype "passive"))
      (node (ref "C35") (pin "2") (pinfunction "2_2") (pintype "passive"))
      (node (ref "C36") (pin "2") (pinfunction "2_2") (pintype "passive"))
      (node (ref "C4") (pin "2") (pinfunction "2_2") (pintype "passive"))
      (node (ref "C5") (pin "2") (pinfunction "2_2") (pintype "passive"))
      (node (ref "C6") (pin "2") (pinfunction "2_2") (pintype "passive"))
      (node (ref "C9") (pin "2") (pinfunction "2_2") (pintype "passive"))
      (node (ref "J1") (pin "5") (pinfunction "5_5") (pintype "passive"))
      (node (ref "J2") (pin "5") (pinfunction "5_5") (pintype "passive"))
      (node (ref "J3") (pin "5") (pinfunction "5_5") (pintype "passive"))
      (node (ref "J4") (pin "5") (pinfunction "5_5") (pintype "passive"))
      (node (ref "P1") (pin "4") (pinfunction "GND_4") (pintype "power_in"))
      (node (ref "R1") (pin "1") (pinfunction "1_1") (pintype "passive"))
      (node (ref "U1") (pin "25") (pinfunction "GND_25") (pintype "power_in"))
      (node (ref "U2") (pin "25") (pinfunction "GND_25") (pintype "power_in"))
      (node (ref "U3") (pin "25") (pinfunction "GND_25") (pintype "power_in"))
      (node (ref "U4") (pin "25") (pinfunction "GND_25") (pintype "power_in"))
      (node (ref "U5") (pin "1") (pinfunction "GND_1") (pintype "power_in"))
      (node (ref "U6") (pin "5") (pinfunction "GND_5") (pintype "power_in"))
      (node (ref "U6") (pin "7") (pinfunction "DC_7") (pintype "passive"))
      (node (ref "U7") (pin "1") (pinfunction "GND_1") (pintype "power_in"))
      (node (ref "U7") (pin "10") (pinfunction "AGND_10") (pintype "power_in"))
      (node (ref "U7") (pin "11") (pinfunction "GND_11") (pintype "power_in"))
      (node (ref "U7") (pin "13") (pinfunction "TEST_13") (pintype "input"))
      (node (ref "U7") (pin "15") (pinfunction "GND_15") (pintype "power_in"))
      (node (ref "U7") (pin "25") (pinfunction "GND_25") (pintype "power_in"))
      (node (ref "U7") (pin "35") (pinfunction "GND_35") (pintype "power_in"))
      (node (ref "U7") (pin "47") (pinfunction "GND_47") (pintype "power_in"))
      (node (ref "U7") (pin "5") (pinfunction "GND_5") (pintype "power_in"))
      (node (ref "U7") (pin "51") (pinfunction "GND_51") (pintype "power_in"))
    )
    (net (code "71") (name "Net-(P1-D+)") (class "Default")
      (node (ref "P1") (pin "3") (pinfunction "D+_3") (pintype "bidirectional"))
      (node (ref "U7") (pin "8") (pinfunction "DP_8") (pintype "input"))
    )
    (net (code "72") (name "Net-(P1-D-)") (class "Default")
      (node (ref "P1") (pin "2") (pinfunction "D-_2") (pintype "bidirectional"))
      (node (ref "U7") (pin "7") (pinfunction "DM_7") (pintype "input"))
    )
    (net (code "73") (name "Net-(U1-C1+)") (class "Default")
      (node (ref "C23") (pin "1") (pinfunction "1_1") (pintype "passive"))
      (node (ref "U1") (pin "28") (pinfunction "C1+_28") (pintype "passive"))
    )
    (net (code "74") (name "Net-(U1-C1-)") (class "Default")
      (node (ref "C23") (pin "2") (pinfunction "2_2") (pintype "passive"))
      (node (ref "U1") (pin "24") (pinfunction "C1-_24") (pintype "passive"))
    )
    (net (code "75") (name "Net-(U1-C2+)") (class "Default")
      (node (ref "C22") (pin "1") (pinfunction "1_1") (pintype "passive"))
      (node (ref "U1") (pin "1") (pinfunction "C2+_1") (pintype "passive"))
    )
    (net (code "76") (name "Net-(U1-C2-)") (class "Default")
      (node (ref "C22") (pin "2") (pinfunction "2_2") (pintype "passive"))
      (node (ref "U1") (pin "2") (pinfunction "C2-_2") (pintype "passive"))
    )
    (net (code "77") (name "Net-(U1-V+)") (class "Default")
      (node (ref "C25") (pin "2") (pinfunction "2_2") (pintype "passive"))
      (node (ref "U1") (pin "27") (pinfunction "V+_27") (pintype "power_in"))
    )
    (net (code "78") (name "Net-(U1-V-)") (class "Default")
      (node (ref "C24") (pin "1") (pinfunction "1_1") (pintype "passive"))
      (node (ref "U1") (pin "3") (pinfunction "V-_3") (pintype "power_in"))
    )
    (net (code "79") (name "Net-(U2-C1+)") (class "Default")
      (node (ref "C13") (pin "1") (pinfunction "1_1") (pintype "passive"))
      (node (ref "U2") (pin "28") (pinfunction "C1+_28") (pintype "passive"))
    )
    (net (code "80") (name "Net-(U2-C1-)") (class "Default")
      (node (ref "C13") (pin "2") (pinfunction "2_2") (pintype "passive"))
      (node (ref "U2") (pin "24") (pinfunction "C1-_24") (pintype "passive"))
    )
    (net (code "81") (name "Net-(U2-C2+)") (class "Default")
      (node (ref "C12") (pin "1") (pinfunction "1_1") (pintype "passive"))
      (node (ref "U2") (pin "1") (pinfunction "C2+_1") (pintype "passive"))
    )
    (net (code "82") (name "Net-(U2-C2-)") (class "Default")
      (node (ref "C12") (pin "2") (pinfunction "2_2") (pintype "passive"))
      (node (ref "U2") (pin "2") (pinfunction "C2-_2") (pintype "passive"))
    )
    (net (code "83") (name "Net-(U2-V+)") (class "Default")
      (node (ref "C15") (pin "2") (pinfunction "2_2") (pintype "passive"))
      (node (ref "U2") (pin "27") (pinfunction "V+_27") (pintype "power_in"))
    )
    (net (code "84") (name "Net-(U2-V-)") (class "Default")
      (node (ref "C14") (pin "1") (pinfunction "1_1") (pintype "passive"))
      (node (ref "U2") (pin "3") (pinfunction "V-_3") (pintype "power_in"))
    )
    (net (code "85") (name "Net-(U3-C1+)") (class "Default")
      (node (ref "C8") (pin "1") (pinfunction "1_1") (pintype "passive"))
      (node (ref "U3") (pin "28") (pinfunction "C1+_28") (pintype "passive"))
    )
    (net (code "86") (name "Net-(U3-C1-)") (class "Default")
      (node (ref "C8") (pin "2") (pinfunction "2_2") (pintype "passive"))
      (node (ref "U3") (pin "24") (pinfunction "C1-_24") (pintype "passive"))
    )
    (net (code "87") (name "Net-(U3-C2+)") (class "Default")
      (node (ref "C7") (pin "1") (pinfunction "1_1") (pintype "passive"))
      (node (ref "U3") (pin "1") (pinfunction "C2+_1") (pintype "passive"))
    )
    (net (code "88") (name "Net-(U3-C2-)") (class "Default")
      (node (ref "C7") (pin "2") (pinfunction "2_2") (pintype "passive"))
      (node (ref "U3") (pin "2") (pinfunction "C2-_2") (pintype "passive"))
    )
    (net (code "89") (name "Net-(U3-V+)") (class "Default")
      (node (ref "C10") (pin "2") (pinfunction "2_2") (pintype "passive"))
      (node (ref "U3") (pin "27") (pinfunction "V+_27") (pintype "power_in"))
    )
    (net (code "90") (name "Net-(U3-V-)") (class "Default")
      (node (ref "C9") (pin "1") (pinfunction "1_1") (pintype "passive"))
      (node (ref "U3") (pin "3") (pinfunction "V-_3") (pintype "power_in"))
    )
    (net (code "91") (name "Net-(U4-C1+)") (class "Default")
      (node (ref "C18") (pin "1") (pinfunction "1_1") (pintype "passive"))
      (node (ref "U4") (pin "28") (pinfunction "C1+_28") (pintype "passive"))
    )
    (net (code "92") (name "Net-(U4-C1-)") (class "Default")
      (node (ref "C18") (pin "2") (pinfunction "2_2") (pintype "passive"))
      (node (ref "U4") (pin "24") (pinfunction "C1-_24") (pintype "passive"))
    )
    (net (code "93") (name "Net-(U4-C2+)") (class "Default")
      (node (ref "C17") (pin "1") (pinfunction "1_1") (pintype "passive"))
      (node (ref "U4") (pin "1") (pinfunction "C2+_1") (pintype "passive"))
    )
    (net (code "94") (name "Net-(U4-C2-)") (class "Default")
      (node (ref "C17") (pin "2") (pinfunction "2_2") (pintype "passive"))
      (node (ref "U4") (pin "2") (pinfunction "C2-_2") (pintype "passive"))
    )
    (net (code "95") (name "Net-(U4-V+)") (class "Default")
      (node (ref "C20") (pin "2") (pinfunction "2_2") (pintype "passive"))
      (node (ref "U4") (pin "27") (pinfunction "V+_27") (pintype "power_in"))
    )
    (net (code "96") (name "Net-(U4-V-)") (class "Default")
      (node (ref "C19") (pin "1") (pinfunction "1_1") (pintype "passive"))
      (node (ref "U4") (pin "3") (pinfunction "V-_3") (pintype "power_in"))
    )
    (net (code "97") (name "Net-(U6-CLK)") (class "Default")
      (node (ref "R5") (pin "1") (pinfunction "1_1") (pintype "passive"))
      (node (ref "U6") (pin "2") (pinfunction "CLK_2") (pintype "input"))
      (node (ref "U7") (pin "62") (pinfunction "EECLK_62") (pintype "output"))
    )
    (net (code "98") (name "Net-(U6-CS)") (class "Default")
      (node (ref "R2") (pin "2") (pinfunction "2_2") (pintype "passive"))
      (node (ref "R6") (pin "1") (pinfunction "1_1") (pintype "passive"))
      (node (ref "U6") (pin "1") (pinfunction "CS_1") (pintype "input"))
      (node (ref "U6") (pin "4") (pinfunction "DO_4") (pintype "tri_state"))
      (node (ref "U7") (pin "63") (pinfunction "EECS_63") (pintype "bidirectional"))
    )
    (net (code "99") (name "Net-(U6-DI)") (class "Default")
      (node (ref "R2") (pin "1") (pinfunction "1_1") (pintype "passive"))
      (node (ref "R4") (pin "1") (pinfunction "1_1") (pintype "passive"))
      (node (ref "U6") (pin "3") (pinfunction "DI_3") (pintype "input"))
      (node (ref "U7") (pin "61") (pinfunction "EEDATA_61") (pintype "bidirectional"))
    )
    (net (code "100") (name "Net-(U7-OSCI)") (class "Default")
      (node (ref "C27") (pin "1") (pinfunction "1_1") (pintype "passive"))
      (node (ref "U7") (pin "2") (pinfunction "OSCI_2") (pintype "input"))
      (node (ref "Y1") (pin "1") (pinfunction "1_1") (pintype "passive"))
    )
    (net (code "101") (name "Net-(U7-OSCO)") (class "Default")
      (node (ref "C28") (pin "1") (pinfunction "1_1") (pintype "passive"))
      (node (ref "U7") (pin "3") (pinfunction "OSCO_3") (pintype "output"))
      (node (ref "Y1") (pin "2") (pinfunction "2_2") (pintype "passive"))
    )
    (net (code "102") (name "Net-(U7-REF)") (class "Default")
      (node (ref "R1") (pin "2") (pinfunction "2_2") (pintype "passive"))
      (node (ref "U7") (pin "6") (pinfunction "REF_6") (pintype "input"))
    )
    (net (code "103") (name "Net-(U7-RESET#)") (class "Default")
      (node (ref "R3") (pin "2") (pinfunction "2_2") (pintype "passive"))
      (node (ref "U7") (pin "14") (pinfunction "RESET#_14") (pintype "input"))
    )
    (net (code "104") (name "Net-(U7-VPHY)") (class "Default")
      (node (ref "C34") (pin "1") (pinfunction "1_1") (pintype "passive"))
      (node (ref "C35") (pin "1") (pinfunction "1_1") (pintype "passive"))
      (node (ref "FB2") (pin "2") (pinfunction "2_2") (pintype "passive"))
      (node (ref "U7") (pin "4") (pinfunction "VPHY_4") (pintype "power_in"))
    )
    (net (code "105") (name "Net-(U7-VPLL)") (class "Default")
      (node (ref "C33") (pin "1") (pinfunction "1_1") (pintype "passive"))
      (node (ref "C36") (pin "1") (pinfunction "1_1") (pintype "passive"))
      (node (ref "FB1") (pin "2") (pinfunction "2_2") (pintype "passive"))
      (node (ref "U7") (pin "9") (pinfunction "VPLL_9") (pintype "power_in"))
    )
    (net (code "106") (name "VCC") (class "Default")
      (node (ref "C31") (pin "1") (pinfunction "1_1") (pintype "passive"))
      (node (ref "P1") (pin "1") (pinfunction "VBUS_1") (pintype "power_in"))
      (node (ref "U5") (pin "3") (pinfunction "VIN_3") (pintype "power_in"))
    )
    (net (code "107") (name "unconnected-(J1-MH2-Pad11)") (class "Default")
      (node (ref "J1") (pin "11") (pinfunction "MH2_11") (pintype "passive"))
    )
    (net (code "108") (name "unconnected-(J2-MH2-Pad11)") (class "Default")
      (node (ref "J2") (pin "11") (pinfunction "MH2_11") (pintype "passive"))
    )
    (net (code "109") (name "unconnected-(J3-MH2-Pad11)") (class "Default")
      (node (ref "J3") (pin "11") (pinfunction "MH2_11") (pintype "passive"))
    )
    (net (code "110") (name "unconnected-(J4-MH2-Pad11)") (class "Default")
      (node (ref "J4") (pin "11") (pinfunction "MH2_11") (pintype "passive"))
    )
    (net (code "111") (name "unconnected-(U1-R1OUTB-Pad21)") (class "Default")
      (node (ref "U1") (pin "21") (pinfunction "R1OUTB_21") (pintype "output"))
    )
    (net (code "112") (name "unconnected-(U1-R2OUTB-Pad20)") (class "Default")
      (node (ref "U1") (pin "20") (pinfunction "R2OUTB_20") (pintype "output"))
    )
    (net (code "113") (name "unconnected-(U2-R1OUTB-Pad21)") (class "Default")
      (node (ref "U2") (pin "21") (pinfunction "R1OUTB_21") (pintype "output"))
    )
    (net (code "114") (name "unconnected-(U2-R2OUTB-Pad20)") (class "Default")
      (node (ref "U2") (pin "20") (pinfunction "R2OUTB_20") (pintype "output"))
    )
    (net (code "115") (name "unconnected-(U3-R1OUTB-Pad21)") (class "Default")
      (node (ref "U3") (pin "21") (pinfunction "R1OUTB_21") (pintype "output"))
    )
    (net (code "116") (name "unconnected-(U3-R2OUTB-Pad20)") (class "Default")
      (node (ref "U3") (pin "20") (pinfunction "R2OUTB_20") (pintype "output"))
    )
    (net (code "117") (name "unconnected-(U4-R1OUTB-Pad21)") (class "Default")
      (node (ref "U4") (pin "21") (pinfunction "R1OUTB_21") (pintype "output"))
    )
    (net (code "118") (name "unconnected-(U4-R2OUTB-Pad20)") (class "Default")
      (node (ref "U4") (pin "20") (pinfunction "R2OUTB_20") (pintype "output"))
    )
  )
)
